# TriacDimmer.net
KiCad netlist of a schematic drawn in EAGLE
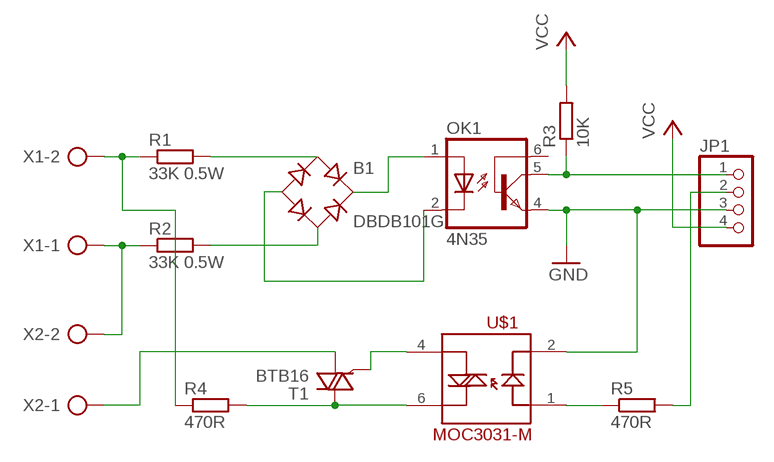
[diagram p0: schematic, sheet 1]

(export (version "E")
  (design (tool "Eeschema 10.0.6"))
  (components
    (comp (ref "B1")
      (value "DBDB101G")
      (footprint "eagle-import:DB")
      (libsource (lib "eagle-import") (part "DB?GDB101"))
    )
    (comp (ref "JP1")
      (value "PINHD-1X4")
      (footprint "eagle-import:1X04")
      (libsource (lib "eagle-import") (part "PINHD-1X4"))
    )
    (comp (ref "OK1")
      (value "4N35")
      (footprint "eagle-import:DIL06")
      (fields (field (name "MF") "FAIRCHILD SEMICONDUCTOR"))
      (libsource (lib "eagle-import") (part "4N35"))
    )
    (comp (ref "R1")
      (value "33K 0.5W")
      (footprint "eagle-import:0207_10")
      (libsource (lib "eagle-import") (part "R-EU_0207/10"))
    )
    (comp (ref "R2")
      (value "33K 0.5W")
      (footprint "eagle-import:0207_10")
      (libsource (lib "eagle-import") (part "R-EU_0207/10"))
    )
    (comp (ref "R3")
      (value "10K")
      (footprint "eagle-import:0207_10")
      (libsource (lib "eagle-import") (part "R-EU_0207/10"))
    )
    (comp (ref "R4")
      (value "470R")
      (footprint "eagle-import:0207_10")
      (libsource (lib "eagle-import") (part "R-EU_0207/10"))
    )
    (comp (ref "R5")
      (value "470R")
      (footprint "eagle-import:0207_10")
      (libsource (lib "eagle-import") (part "R-EU_0207/10"))
    )
    (comp (ref "T1")
      (value "BTB16")
      (footprint "eagle-import:TO220BV")
      (libsource (lib "eagle-import") (part "BT138-V"))
    )
    (comp (ref "U$1")
      (value "MOC3031-M")
      (footprint "eagle-import:DIL06")
      (libsource (lib "eagle-import") (part "MOC3031-M"))
    )
    (comp (ref "X1")
      (value "AK300/2")
      (footprint "eagle-import:AK300_2")
      (libsource (lib "eagle-import") (part "AK300/2"))
    )
    (comp (ref "X2")
      (value "AK300/2")
      (footprint "eagle-import:AK300_2")
      (libsource (lib "eagle-import") (part "AK300/2"))
    )
  )
  (nets
    (net (code "1") (name "GND") (class "Default")
      (node (ref "JP1") (pin "3") (pinfunction "3_3") (pintype "passive"))
      (node (ref "OK1") (pin "4") (pinfunction "EMI_4") (pintype "passive"))
      (node (ref "U$1") (pin "2") (pinfunction "2_2") (pintype "bidirectional"))
    )
    (net (code "2") (name "Net-(B1-PadAC1)") (class "Default")
      (node (ref "B1") (pin "AC1") (pinfunction "AC1_AC1") (pintype "passive"))
      (node (ref "R1") (pin "2") (pinfunction "2_2") (pintype "passive"))
    )
    (net (code "3") (name "Net-(B1-PadAC2)") (class "Default")
      (node (ref "B1") (pin "AC2") (pinfunction "AC2_AC2") (pintype "passive"))
      (node (ref "R2") (pin "2") (pinfunction "2_2") (pintype "passive"))
    )
    (net (code "4") (name "Net-(JP1-Pad2)") (class "Default")
      (node (ref "JP1") (pin "2") (pinfunction "2_2") (pintype "passive"))
      (node (ref "R5") (pin "2") (pinfunction "2_2") (pintype "passive"))
    )
    (net (code "5") (name "Net-(OK1-A)") (class "Default")
      (node (ref "B1") (pin "+") (pinfunction "+_+") (pintype "passive"))
      (node (ref "OK1") (pin "1") (pinfunction "A_1") (pintype "passive"))
    )
    (net (code "6") (name "Net-(OK1-C)") (class "Default")
      (node (ref "B1") (pin "-") (pinfunction "-_-") (pintype "passive"))
      (node (ref "OK1") (pin "2") (pinfunction "C_2") (pintype "passive"))
    )
    (net (code "7") (name "Net-(OK1-COL)") (class "Default")
      (node (ref "JP1") (pin "1") (pinfunction "1_1") (pintype "passive"))
      (node (ref "OK1") (pin "5") (pinfunction "COL_5") (pintype "passive"))
      (node (ref "R3") (pin "1") (pinfunction "1_1") (pintype "passive"))
    )
    (net (code "8") (name "Net-(R5-Pad1)") (class "Default")
      (node (ref "R5") (pin "1") (pinfunction "1_1") (pintype "passive"))
      (node (ref "U$1") (pin "1") (pinfunction "1_1") (pintype "bidirectional"))
    )
    (net (code "9") (name "Net-(T1-A1)") (class "Default")
      (node (ref "T1") (pin "T1") (pinfunction "A1_T1") (pintype "passive"))
      (node (ref "X2") (pin "1") (pinfunction "KL_1") (pintype "passive"))
    )
    (net (code "10") (name "Net-(T1-A2)") (class "Default")
      (node (ref "R4") (pin "2") (pinfunction "2_2") (pintype "passive"))
      (node (ref "T1") (pin "T2") (pinfunction "A2_T2") (pintype "passive"))
      (node (ref "U$1") (pin "6") (pinfunction "6_6") (pintype "bidirectional"))
    )
    (net (code "11") (name "Net-(T1-PadG)") (class "Default")
      (node (ref "T1") (pin "G") (pinfunction "G_G") (pintype "passive"))
      (node (ref "U$1") (pin "4") (pinfunction "4_4") (pintype "bidirectional"))
    )
    (net (code "12") (name "Net-(X1A-KL)") (class "Default")
      (node (ref "R2") (pin "1") (pinfunction "1_1") (pintype "passive"))
      (node (ref "X1") (pin "1") (pinfunction "KL_1") (pintype "passive"))
      (node (ref "X2") (pin "2") (pinfunction "KL_2") (pintype "passive"))
    )
    (net (code "13") (name "Net-(X1B-KL)") (class "Default")
      (node (ref "R1") (pin "1") (pinfunction "1_1") (pintype "passive"))
      (node (ref "R4") (pin "1") (pinfunction "1_1") (pintype "passive"))
      (node (ref "X1") (pin "2") (pinfunction "KL_2") (pintype "passive"))
    )
    (net (code "14") (name "VCC") (class "Default")
      (node (ref "JP1") (pin "4") (pinfunction "4_4") (pintype "passive"))
      (node (ref "R3") (pin "2") (pinfunction "2_2") (pintype "passive"))
    )
    (net (code "15") (name "unconnected-(OK1-BAS-Pad6)") (class "Default")
      (node (ref "OK1") (pin "6") (pinfunction "BAS_6") (pintype "passive"))
    )
  )
)
